# TCB_MAIN.net
KiCad netlist of a schematic drawn in EAGLE
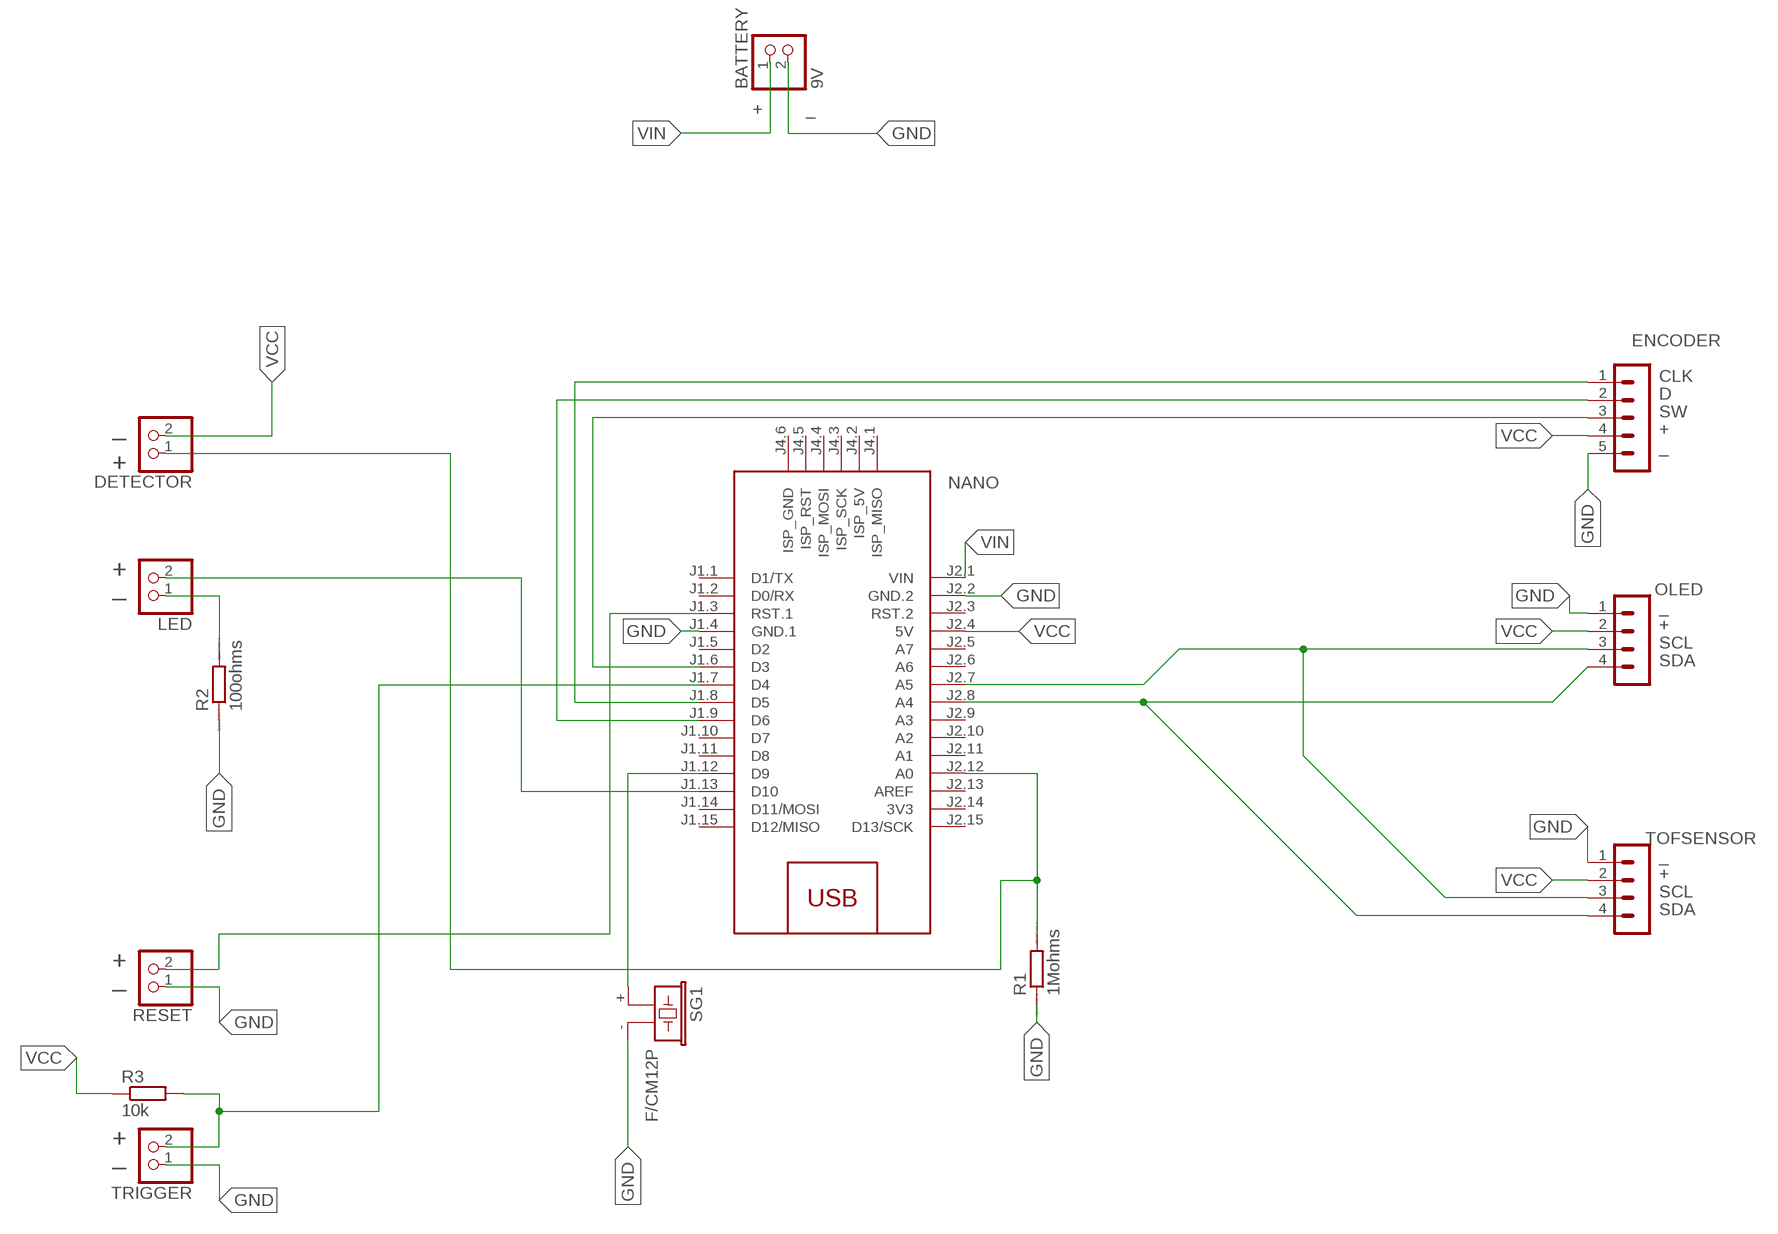
[diagram p0: schematic, sheet 1]

(export (version "E")
  (design (tool "Eeschema 10.0.6"))
  (components
    (comp (ref "BATTERY")
      (value "9V")
      (footprint "eagle-import:1X02")
      (libsource (lib "eagle-import") (part "PINHD-1X2"))
    )
    (comp (ref "DETECTOR")
      (value "PINHD-1X2")
      (footprint "eagle-import:1X02")
      (libsource (lib "eagle-import") (part "PINHD-1X2"))
    )
    (comp (ref "ENCODER")
      (value "MA05-1")
      (footprint "eagle-import:MA05-1")
      (libsource (lib "eagle-import") (part "MA05-1"))
    )
    (comp (ref "LED")
      (value "PINHD-1X2")
      (footprint "eagle-import:1X02")
      (libsource (lib "eagle-import") (part "PINHD-1X2"))
    )
    (comp (ref "NANO")
      (value "ARDUINO-NANO-3.0#ISP")
      (footprint "eagle-import:ARDUINO-NANO-3.0#ISP")
      (libsource (lib "eagle-import") (part "ARDUINO-NANO-3.0#ISP"))
    )
    (comp (ref "OLED")
      (value "MA04-1")
      (footprint "eagle-import:MA04-1")
      (libsource (lib "eagle-import") (part "MA04-1"))
    )
    (comp (ref "R1")
      (value "1Mohms")
      (footprint "eagle-import:0204_7")
      (libsource (lib "eagle-import") (part "R0204/7"))
    )
    (comp (ref "R2")
      (value "100ohms")
      (footprint "eagle-import:0204_7")
      (libsource (lib "eagle-import") (part "R0204/7"))
    )
    (comp (ref "R3")
      (value "10k")
      (footprint "eagle-import:0204_7")
      (libsource (lib "eagle-import") (part "R-EU_0204/7"))
    )
    (comp (ref "RESET")
      (value "PINHD-1X2")
      (footprint "eagle-import:1X02")
      (libsource (lib "eagle-import") (part "PINHD-1X2"))
    )
    (comp (ref "SG1")
      (value "F/CM12P")
      (footprint "eagle-import:F_CM12P")
      (libsource (lib "eagle-import") (part "F/CM12P"))
    )
    (comp (ref "TOFSENSOR")
      (value "MA04-1")
      (footprint "eagle-import:MA04-1")
      (libsource (lib "eagle-import") (part "MA04-1"))
    )
    (comp (ref "TRIGGER")
      (value "PINHD-1X2")
      (footprint "eagle-import:1X02")
      (libsource (lib "eagle-import") (part "PINHD-1X2"))
    )
  )
  (nets
    (net (code "1") (name "/3V3") (class "Default")
      (node (ref "NANO") (pin "J2.14") (pinfunction "3V3_J2.14") (pintype "power_in"))
    )
    (net (code "2") (name "GND") (class "Default")
      (node (ref "BATTERY") (pin "2") (pinfunction "2_2") (pintype "passive"))
      (node (ref "ENCODER") (pin "5") (pinfunction "5_5") (pintype "passive"))
      (node (ref "NANO") (pin "J1.4") (pinfunction "GND.1_J1.4") (pintype "power_in"))
      (node (ref "NANO") (pin "J2.2") (pinfunction "GND.2_J2.2") (pintype "power_in"))
      (node (ref "OLED") (pin "1") (pinfunction "1_1") (pintype "passive"))
      (node (ref "R1") (pin "1") (pinfunction "1_1") (pintype "passive"))
      (node (ref "R2") (pin "1") (pinfunction "1_1") (pintype "passive"))
      (node (ref "RESET") (pin "1") (pinfunction "1_1") (pintype "passive"))
      (node (ref "SG1") (pin "-") (pinfunction "2_-") (pintype "passive"))
      (node (ref "TOFSENSOR") (pin "1") (pinfunction "1_1") (pintype "passive"))
      (node (ref "TRIGGER") (pin "1") (pinfunction "1_1") (pintype "passive"))
    )
    (net (code "3") (name "Net-(LED-Pad1)") (class "Default")
      (node (ref "LED") (pin "1") (pinfunction "1_1") (pintype "passive"))
      (node (ref "R2") (pin "2") (pinfunction "2_2") (pintype "passive"))
    )
    (net (code "4") (name "Net-(NANO-A0)") (class "Default")
      (node (ref "DETECTOR") (pin "1") (pinfunction "1_1") (pintype "passive"))
      (node (ref "NANO") (pin "J2.12") (pinfunction "A0_J2.12") (pintype "bidirectional"))
      (node (ref "R1") (pin "2") (pinfunction "2_2") (pintype "passive"))
    )
    (net (code "5") (name "Net-(NANO-A4)") (class "Default")
      (node (ref "NANO") (pin "J2.8") (pinfunction "A4_J2.8") (pintype "bidirectional"))
      (node (ref "OLED") (pin "4") (pinfunction "4_4") (pintype "passive"))
      (node (ref "TOFSENSOR") (pin "4") (pinfunction "4_4") (pintype "passive"))
    )
    (net (code "6") (name "Net-(NANO-A5)") (class "Default")
      (node (ref "NANO") (pin "J2.7") (pinfunction "A5_J2.7") (pintype "bidirectional"))
      (node (ref "OLED") (pin "3") (pinfunction "3_3") (pintype "passive"))
      (node (ref "TOFSENSOR") (pin "3") (pinfunction "3_3") (pintype "passive"))
    )
    (net (code "7") (name "Net-(NANO-D3)") (class "Default")
      (node (ref "ENCODER") (pin "3") (pinfunction "3_3") (pintype "passive"))
      (node (ref "NANO") (pin "J1.6") (pinfunction "D3_J1.6") (pintype "bidirectional"))
    )
    (net (code "8") (name "Net-(NANO-D4)") (class "Default")
      (node (ref "NANO") (pin "J1.7") (pinfunction "D4_J1.7") (pintype "bidirectional"))
      (node (ref "R3") (pin "2") (pinfunction "2_2") (pintype "passive"))
      (node (ref "TRIGGER") (pin "2") (pinfunction "2_2") (pintype "passive"))
    )
    (net (code "9") (name "Net-(NANO-D5)") (class "Default")
      (node (ref "ENCODER") (pin "1") (pinfunction "1_1") (pintype "passive"))
      (node (ref "NANO") (pin "J1.8") (pinfunction "D5_J1.8") (pintype "bidirectional"))
    )
    (net (code "10") (name "Net-(NANO-D6)") (class "Default")
      (node (ref "ENCODER") (pin "2") (pinfunction "2_2") (pintype "passive"))
      (node (ref "NANO") (pin "J1.9") (pinfunction "D6_J1.9") (pintype "bidirectional"))
    )
    (net (code "11") (name "Net-(NANO-D9)") (class "Default")
      (node (ref "NANO") (pin "J1.12") (pinfunction "D9_J1.12") (pintype "bidirectional"))
      (node (ref "SG1") (pin "+") (pinfunction "1_+") (pintype "passive"))
    )
    (net (code "12") (name "Net-(NANO-D10)") (class "Default")
      (node (ref "LED") (pin "2") (pinfunction "2_2") (pintype "passive"))
      (node (ref "NANO") (pin "J1.13") (pinfunction "D10_J1.13") (pintype "bidirectional"))
    )
    (net (code "13") (name "Net-(NANO-RST.1)") (class "Default")
      (node (ref "NANO") (pin "J1.3") (pinfunction "RST.1_J1.3") (pintype "bidirectional"))
      (node (ref "RESET") (pin "2") (pinfunction "2_2") (pintype "passive"))
    )
    (net (code "14") (name "VCC") (class "Default")
      (node (ref "DETECTOR") (pin "2") (pinfunction "2_2") (pintype "passive"))
      (node (ref "ENCODER") (pin "4") (pinfunction "4_4") (pintype "passive"))
      (node (ref "NANO") (pin "J2.4") (pinfunction "5V_J2.4") (pintype "power_in"))
      (node (ref "OLED") (pin "2") (pinfunction "2_2") (pintype "passive"))
      (node (ref "R3") (pin "1") (pinfunction "1_1") (pintype "passive"))
      (node (ref "TOFSENSOR") (pin "2") (pinfunction "2_2") (pintype "passive"))
    )
    (net (code "15") (name "VIN") (class "Default")
      (node (ref "BATTERY") (pin "1") (pinfunction "1_1") (pintype "passive"))
      (node (ref "NANO") (pin "J2.1") (pinfunction "VIN_J2.1") (pintype "power_in"))
    )
    (net (code "16") (name "unconnected-(NANO-A1-PadJ2.11)") (class "Default")
      (node (ref "NANO") (pin "J2.11") (pinfunction "A1_J2.11") (pintype "bidirectional"))
    )
    (net (code "17") (name "unconnected-(NANO-A2-PadJ2.10)") (class "Default")
      (node (ref "NANO") (pin "J2.10") (pinfunction "A2_J2.10") (pintype "bidirectional"))
    )
    (net (code "18") (name "unconnected-(NANO-A3-PadJ2.9)") (class "Default")
      (node (ref "NANO") (pin "J2.9") (pinfunction "A3_J2.9") (pintype "bidirectional"))
    )
    (net (code "19") (name "unconnected-(NANO-A6-PadJ2.6)") (class "Default")
      (node (ref "NANO") (pin "J2.6") (pinfunction "A6_J2.6") (pintype "bidirectional"))
    )
    (net (code "20") (name "unconnected-(NANO-A7-PadJ2.5)") (class "Default")
      (node (ref "NANO") (pin "J2.5") (pinfunction "A7_J2.5") (pintype "bidirectional"))
    )
    (net (code "21") (name "unconnected-(NANO-AREF-PadJ2.13)") (class "Default")
      (node (ref "NANO") (pin "J2.13") (pinfunction "AREF_J2.13") (pintype "bidirectional"))
    )
    (net (code "22") (name "unconnected-(NANO-D0{slash}RX-PadJ1.2)") (class "Default")
      (node (ref "NANO") (pin "J1.2") (pinfunction "D0/RX_J1.2") (pintype "bidirectional"))
    )
    (net (code "23") (name "unconnected-(NANO-D1{slash}TX-PadJ1.1)") (class "Default")
      (node (ref "NANO") (pin "J1.1") (pinfunction "D1/TX_J1.1") (pintype "bidirectional"))
    )
    (net (code "24") (name "unconnected-(NANO-D2-PadJ1.5)") (class "Default")
      (node (ref "NANO") (pin "J1.5") (pinfunction "D2_J1.5") (pintype "bidirectional"))
    )
    (net (code "25") (name "unconnected-(NANO-D7-PadJ1.10)") (class "Default")
      (node (ref "NANO") (pin "J1.10") (pinfunction "D7_J1.10") (pintype "bidirectional"))
    )
    (net (code "26") (name "unconnected-(NANO-D8-PadJ1.11)") (class "Default")
      (node (ref "NANO") (pin "J1.11") (pinfunction "D8_J1.11") (pintype "bidirectional"))
    )
    (net (code "27") (name "unconnected-(NANO-D11{slash}MOSI-PadJ1.14)") (class "Default")
      (node (ref "NANO") (pin "J1.14") (pinfunction "D11/MOSI_J1.14") (pintype "bidirectional"))
    )
    (net (code "28") (name "unconnected-(NANO-D12{slash}MISO-PadJ1.15)") (class "Default")
      (node (ref "NANO") (pin "J1.15") (pinfunction "D12/MISO_J1.15") (pintype "bidirectional"))
    )
    (net (code "29") (name "unconnected-(NANO-D13{slash}SCK-PadJ2.15)") (class "Default")
      (node (ref "NANO") (pin "J2.15") (pinfunction "D13/SCK_J2.15") (pintype "bidirectional"))
    )
    (net (code "30") (name "unconnected-(NANO-ISP_5V-PadJ4.2)") (class "Default")
      (node (ref "NANO") (pin "J4.2") (pinfunction "ISP_5V_J4.2") (pintype "bidirectional"))
    )
    (net (code "31") (name "unconnected-(NANO-ISP_GND-PadJ4.6)") (class "Default")
      (node (ref "NANO") (pin "J4.6") (pinfunction "ISP_GND_J4.6") (pintype "bidirectional"))
    )
    (net (code "32") (name "unconnected-(NANO-ISP_MISO-PadJ4.1)") (class "Default")
      (node (ref "NANO") (pin "J4.1") (pinfunction "ISP_MISO_J4.1") (pintype "bidirectional"))
    )
    (net (code "33") (name "unconnected-(NANO-ISP_MOSI-PadJ4.4)") (class "Default")
      (node (ref "NANO") (pin "J4.4") (pinfunction "ISP_MOSI_J4.4") (pintype "bidirectional"))
    )
    (net (code "34") (name "unconnected-(NANO-ISP_RST-PadJ4.5)") (class "Default")
      (node (ref "NANO") (pin "J4.5") (pinfunction "ISP_RST_J4.5") (pintype "bidirectional"))
    )
    (net (code "35") (name "unconnected-(NANO-ISP_SCK-PadJ4.3)") (class "Default")
      (node (ref "NANO") (pin "J4.3") (pinfunction "ISP_SCK_J4.3") (pintype "bidirectional"))
    )
    (net (code "36") (name "unconnected-(NANO-RST.2-PadJ2.3)") (class "Default")
      (node (ref "NANO") (pin "J2.3") (pinfunction "RST.2_J2.3") (pintype "bidirectional"))
    )
  )
)
